# LCD1602_IIC_Interface_Board.net
KiCad netlist of a schematic drawn in EAGLE
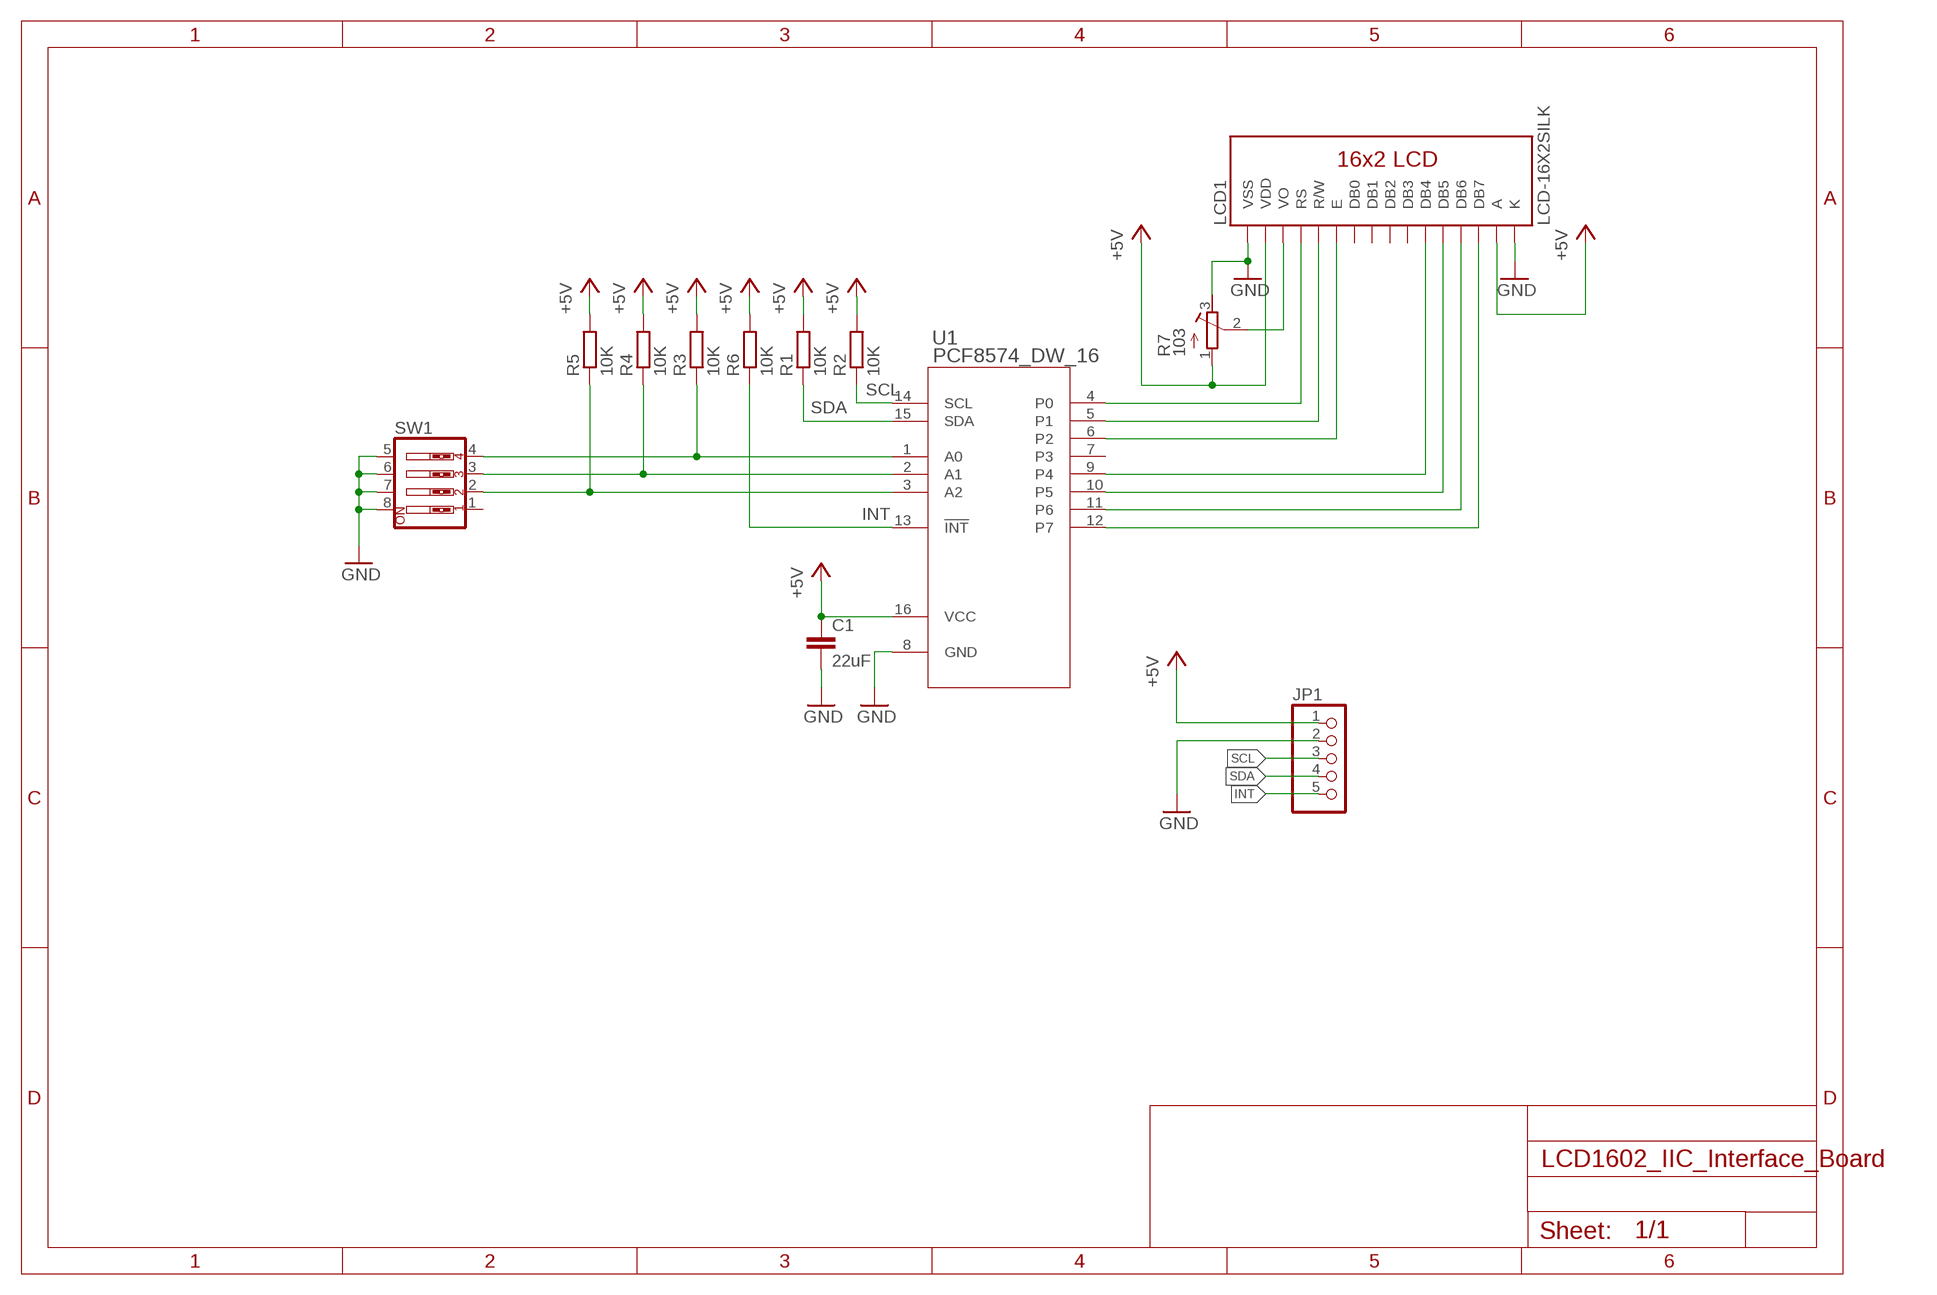
[diagram p0: schematic, sheet 1]

(export (version "E")
  (design (tool "Eeschema 10.0.6"))
  (components
    (comp (ref "C1")
      (value "22uF")
      (footprint "eagle-import:C1206")
      (libsource (lib "eagle-import") (part "C-EUC1206"))
    )
    (comp (ref "JP1")
      (value "PINHD-1X5")
      (footprint "eagle-import:1X05")
      (libsource (lib "eagle-import") (part "PINHD-1X5"))
    )
    (comp (ref "LCD1")
      (value "LCD-16X2SILK")
      (footprint "eagle-import:LCD-16X2")
      (libsource (lib "eagle-import") (part "LCD-16X2SILK"))
    )
    (comp (ref "R1")
      (value "10K")
      (footprint "eagle-import:R0603")
      (libsource (lib "eagle-import") (part "R-EU_R0603"))
    )
    (comp (ref "R2")
      (value "10K")
      (footprint "eagle-import:R0603")
      (libsource (lib "eagle-import") (part "R-EU_R0603"))
    )
    (comp (ref "R3")
      (value "10K")
      (footprint "eagle-import:R0603")
      (libsource (lib "eagle-import") (part "R-EU_R0603"))
    )
    (comp (ref "R4")
      (value "10K")
      (footprint "eagle-import:R0603")
      (libsource (lib "eagle-import") (part "R-EU_R0603"))
    )
    (comp (ref "R5")
      (value "10K")
      (footprint "eagle-import:R0603")
      (libsource (lib "eagle-import") (part "R-EU_R0603"))
    )
    (comp (ref "R6")
      (value "10K")
      (footprint "eagle-import:R0603")
      (libsource (lib "eagle-import") (part "R-EU_R0603"))
    )
    (comp (ref "R7")
      (value "103")
      (footprint "eagle-import:RTRIM3296W")
      (libsource (lib "eagle-import") (part "R-TRIMM3296W"))
    )
    (comp (ref "SW1")
      (value "SW_DIP-4")
      (footprint "eagle-import:EDG-04")
      (libsource (lib "eagle-import") (part "SW_DIP-4"))
    )
    (comp (ref "U1")
      (value "PCF8574_DW_16")
      (footprint "eagle-import:DW16")
      (fields (field (name "MANUFACTURER_PART_NUMBER") "pcf8574_dw_16"))
      (libsource (lib "eagle-import") (part "PCF8574_DW_16"))
    )
  )
  (nets
    (net (code "1") (name "+5V") (class "Default")
      (node (ref "C1") (pin "1") (pinfunction "1_1") (pintype "passive"))
      (node (ref "JP1") (pin "1") (pinfunction "1_1") (pintype "passive"))
      (node (ref "LCD1") (pin "15") (pinfunction "A_15") (pintype "power_in"))
      (node (ref "LCD1") (pin "2") (pinfunction "VDD_2") (pintype "power_in"))
      (node (ref "R1") (pin "2") (pinfunction "2_2") (pintype "passive"))
      (node (ref "R2") (pin "2") (pinfunction "2_2") (pintype "passive"))
      (node (ref "R3") (pin "2") (pinfunction "2_2") (pintype "passive"))
      (node (ref "R4") (pin "2") (pinfunction "2_2") (pintype "passive"))
      (node (ref "R5") (pin "2") (pinfunction "2_2") (pintype "passive"))
      (node (ref "R6") (pin "2") (pinfunction "2_2") (pintype "passive"))
      (node (ref "R7") (pin "1") (pinfunction "A_1") (pintype "passive"))
      (node (ref "U1") (pin "16") (pinfunction "VCC_16") (pintype "power_in"))
    )
    (net (code "2") (name "GND") (class "Default")
      (node (ref "C1") (pin "2") (pinfunction "2_2") (pintype "passive"))
      (node (ref "JP1") (pin "2") (pinfunction "2_2") (pintype "passive"))
      (node (ref "LCD1") (pin "1") (pinfunction "VSS_1") (pintype "power_in"))
      (node (ref "LCD1") (pin "16") (pinfunction "K_16") (pintype "power_in"))
      (node (ref "R7") (pin "3") (pinfunction "E_3") (pintype "passive"))
      (node (ref "SW1") (pin "5") (pinfunction "5_5") (pintype "passive"))
      (node (ref "SW1") (pin "6") (pinfunction "6_6") (pintype "passive"))
      (node (ref "SW1") (pin "7") (pinfunction "7_7") (pintype "passive"))
      (node (ref "SW1") (pin "8") (pinfunction "8_8") (pintype "passive"))
      (node (ref "U1") (pin "8") (pinfunction "GND_8") (pintype "power_in"))
    )
    (net (code "3") (name "INT") (class "Default")
      (node (ref "JP1") (pin "5") (pinfunction "5_5") (pintype "passive"))
      (node (ref "R6") (pin "1") (pinfunction "1_1") (pintype "passive"))
      (node (ref "U1") (pin "13") (pinfunction "~{INT}_13") (pintype "output"))
    )
    (net (code "4") (name "Net-(LCD1-DB4)") (class "Default")
      (node (ref "LCD1") (pin "11") (pinfunction "DB4_11") (pintype "bidirectional"))
      (node (ref "U1") (pin "9") (pinfunction "P4_9") (pintype "bidirectional"))
    )
    (net (code "5") (name "Net-(LCD1-DB5)") (class "Default")
      (node (ref "LCD1") (pin "12") (pinfunction "DB5_12") (pintype "bidirectional"))
      (node (ref "U1") (pin "10") (pinfunction "P5_10") (pintype "bidirectional"))
    )
    (net (code "6") (name "Net-(LCD1-DB6)") (class "Default")
      (node (ref "LCD1") (pin "13") (pinfunction "DB6_13") (pintype "bidirectional"))
      (node (ref "U1") (pin "11") (pinfunction "P6_11") (pintype "bidirectional"))
    )
    (net (code "7") (name "Net-(LCD1-DB7)") (class "Default")
      (node (ref "LCD1") (pin "14") (pinfunction "DB7_14") (pintype "bidirectional"))
      (node (ref "U1") (pin "12") (pinfunction "P7_12") (pintype "bidirectional"))
    )
    (net (code "8") (name "Net-(LCD1-E)") (class "Default")
      (node (ref "LCD1") (pin "6") (pinfunction "E_6") (pintype "input"))
      (node (ref "U1") (pin "6") (pinfunction "P2_6") (pintype "bidirectional"))
    )
    (net (code "9") (name "Net-(LCD1-RS)") (class "Default")
      (node (ref "LCD1") (pin "4") (pinfunction "RS_4") (pintype "input"))
      (node (ref "U1") (pin "4") (pinfunction "P0_4") (pintype "bidirectional"))
    )
    (net (code "10") (name "Net-(LCD1-R{slash}W)") (class "Default")
      (node (ref "LCD1") (pin "5") (pinfunction "R/W_5") (pintype "input"))
      (node (ref "U1") (pin "5") (pinfunction "P1_5") (pintype "bidirectional"))
    )
    (net (code "11") (name "Net-(LCD1-VO)") (class "Default")
      (node (ref "LCD1") (pin "3") (pinfunction "VO_3") (pintype "bidirectional"))
      (node (ref "R7") (pin "2") (pinfunction "S_2") (pintype "passive"))
    )
    (net (code "12") (name "Net-(U1-A0)") (class "Default")
      (node (ref "R3") (pin "1") (pinfunction "1_1") (pintype "passive"))
      (node (ref "SW1") (pin "4") (pinfunction "4_4") (pintype "passive"))
      (node (ref "U1") (pin "1") (pinfunction "A0_1") (pintype "input"))
    )
    (net (code "13") (name "Net-(U1-A1)") (class "Default")
      (node (ref "R4") (pin "1") (pinfunction "1_1") (pintype "passive"))
      (node (ref "SW1") (pin "3") (pinfunction "3_3") (pintype "passive"))
      (node (ref "U1") (pin "2") (pinfunction "A1_2") (pintype "input"))
    )
    (net (code "14") (name "Net-(U1-A2)") (class "Default")
      (node (ref "R5") (pin "1") (pinfunction "1_1") (pintype "passive"))
      (node (ref "SW1") (pin "2") (pinfunction "2_2") (pintype "passive"))
      (node (ref "U1") (pin "3") (pinfunction "A2_3") (pintype "input"))
    )
    (net (code "15") (name "SCL") (class "Default")
      (node (ref "JP1") (pin "3") (pinfunction "3_3") (pintype "passive"))
      (node (ref "R2") (pin "1") (pinfunction "1_1") (pintype "passive"))
      (node (ref "U1") (pin "14") (pinfunction "SCL_14") (pintype "passive"))
    )
    (net (code "16") (name "SDA") (class "Default")
      (node (ref "JP1") (pin "4") (pinfunction "4_4") (pintype "passive"))
      (node (ref "R1") (pin "1") (pinfunction "1_1") (pintype "passive"))
      (node (ref "U1") (pin "15") (pinfunction "SDA_15") (pintype "passive"))
    )
    (net (code "17") (name "unconnected-(LCD1-DB0-Pad7)") (class "Default")
      (node (ref "LCD1") (pin "7") (pinfunction "DB0_7") (pintype "bidirectional"))
    )
    (net (code "18") (name "unconnected-(LCD1-DB1-Pad8)") (class "Default")
      (node (ref "LCD1") (pin "8") (pinfunction "DB1_8") (pintype "bidirectional"))
    )
    (net (code "19") (name "unconnected-(LCD1-DB2-Pad9)") (class "Default")
      (node (ref "LCD1") (pin "9") (pinfunction "DB2_9") (pintype "bidirectional"))
    )
    (net (code "20") (name "unconnected-(LCD1-DB3-Pad10)") (class "Default")
      (node (ref "LCD1") (pin "10") (pinfunction "DB3_10") (pintype "bidirectional"))
    )
    (net (code "21") (name "unconnected-(SW1-Pad1)") (class "Default")
      (node (ref "SW1") (pin "1") (pinfunction "1_1") (pintype "passive"))
    )
    (net (code "22") (name "unconnected-(U1-P3-Pad7)") (class "Default")
      (node (ref "U1") (pin "7") (pinfunction "P3_7") (pintype "bidirectional"))
    )
  )
)
